# main.net
KiCad netlist of a schematic drawn in EAGLE
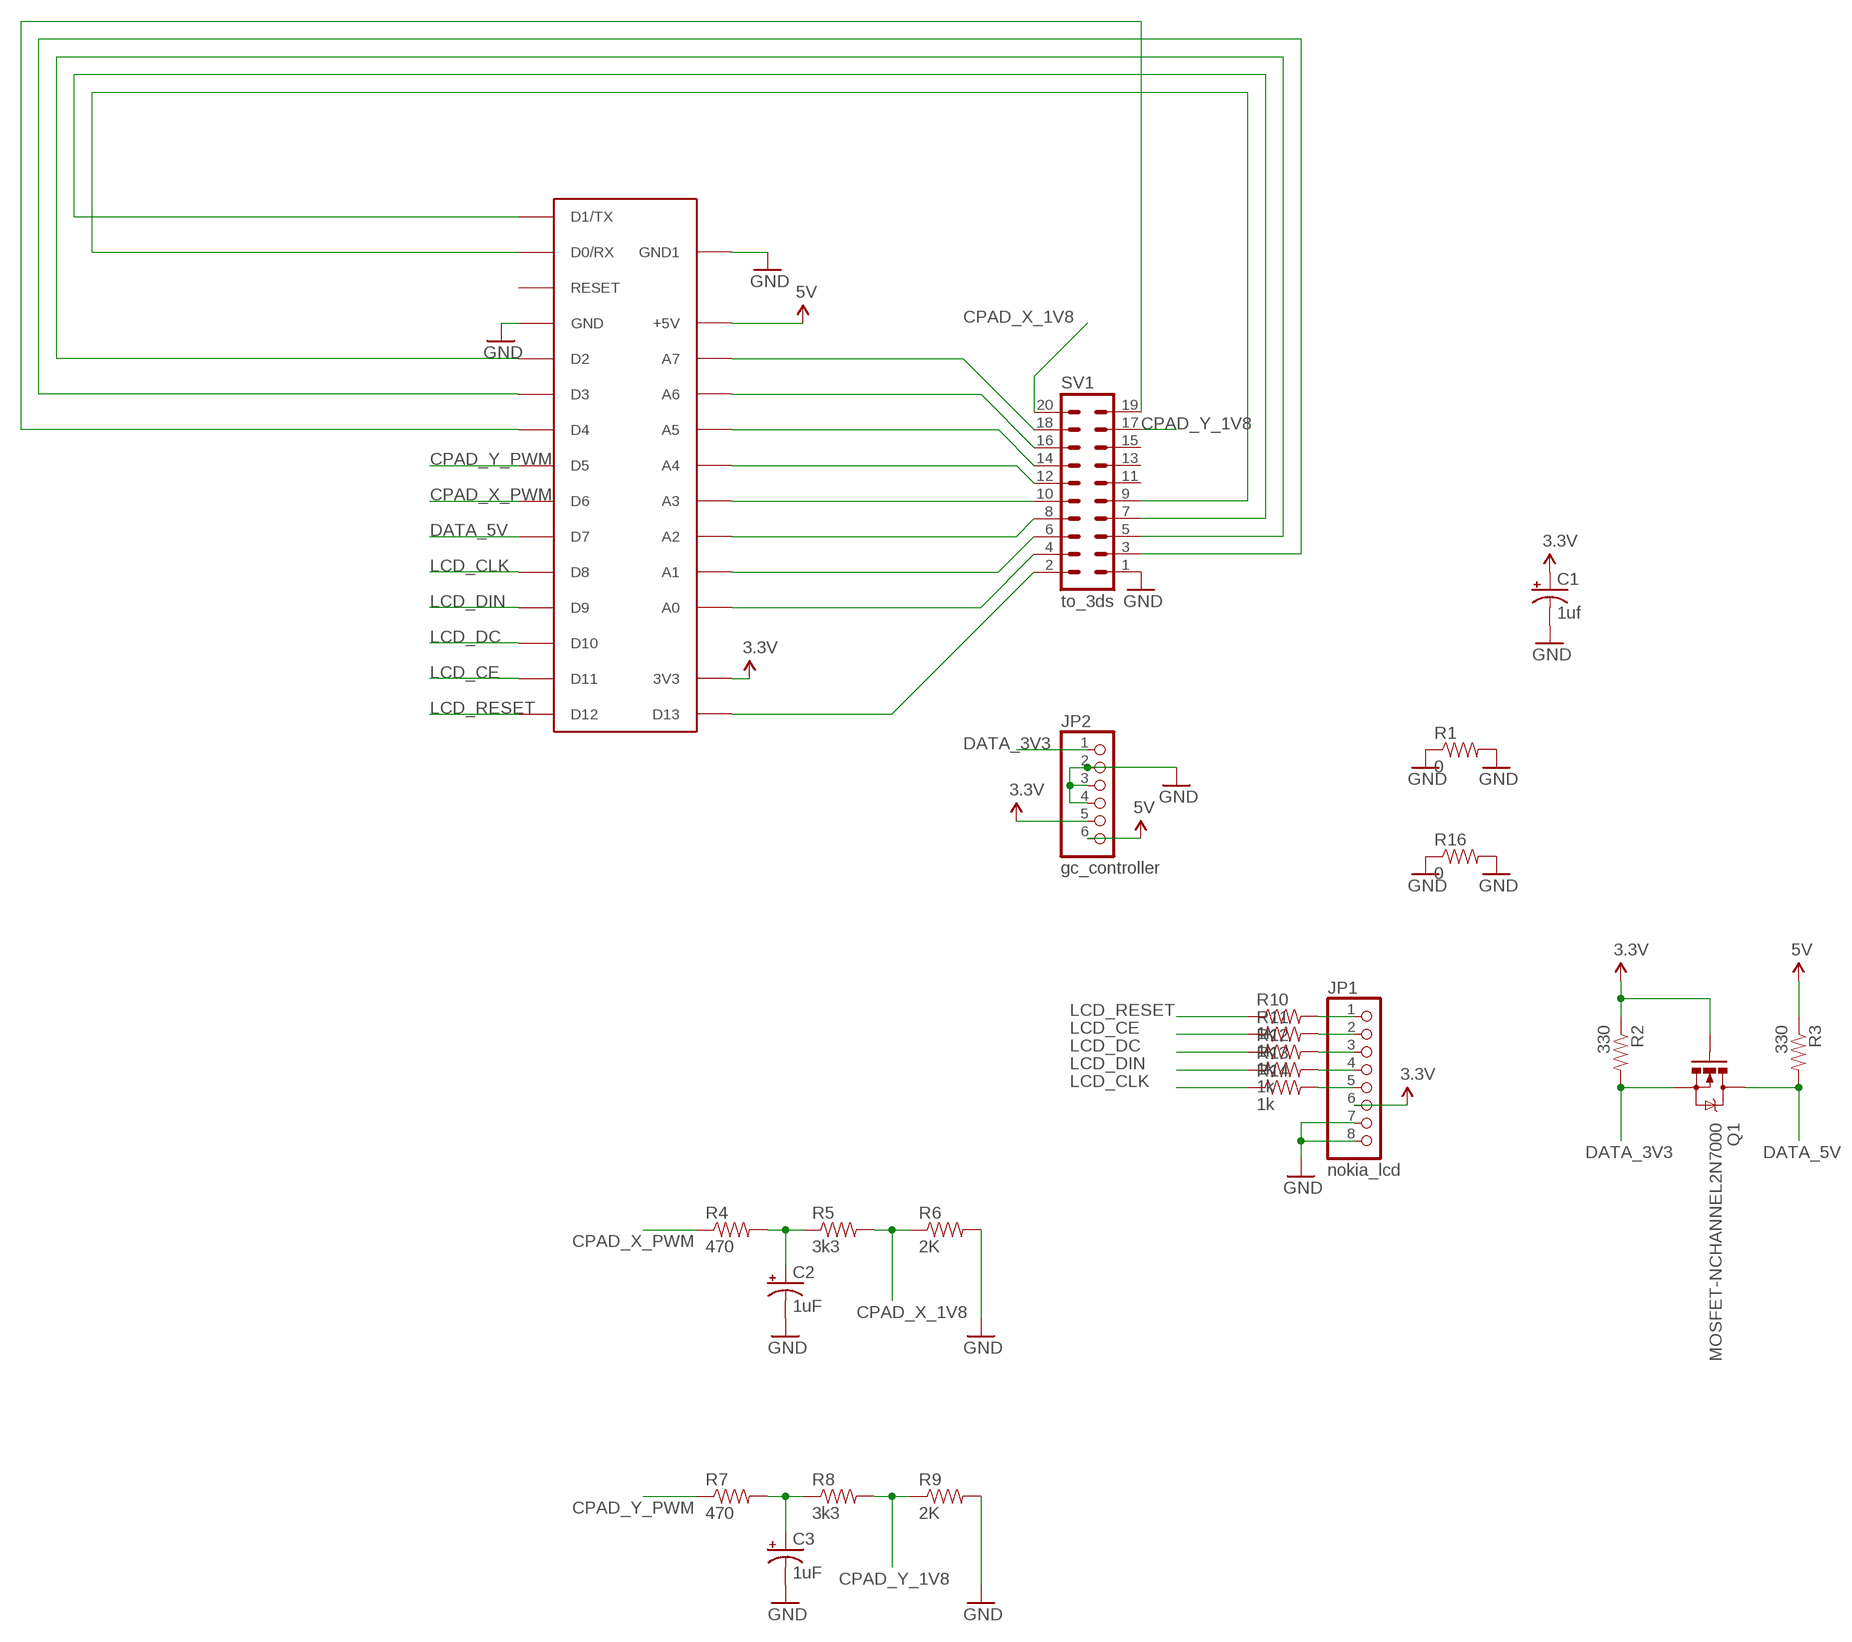
[diagram p0: schematic, sheet 1]

(export (version "E")
  (design (tool "Eeschema 10.0.6"))
  (components
    (comp (ref "C1")
      (value "1uf")
      (footprint "eagle-import:CPOL-RADIAL-10UF-25V")
      (libsource (lib "eagle-import") (part "CAP_POLPTH2"))
    )
    (comp (ref "C2")
      (value "1uF")
      (footprint "eagle-import:CPOL-RADIAL-10UF-25V")
      (libsource (lib "eagle-import") (part "CAP_POLPTH2"))
    )
    (comp (ref "C3")
      (value "1uF")
      (footprint "eagle-import:CPOL-RADIAL-10UF-25V")
      (libsource (lib "eagle-import") (part "CAP_POLPTH2"))
    )
    (comp (ref "JP1")
      (value "nokia_lcd")
      (footprint "eagle-import:1X08-CLEANBIG")
      (libsource (lib "eagle-import") (part "PINHD-1X8CLEANBIG"))
    )
    (comp (ref "JP2")
      (value "gc_controller")
      (footprint "eagle-import:1X06")
      (libsource (lib "eagle-import") (part "PINHD-1X6"))
    )
    (comp (ref "Q1")
      (value "MOSFET-NCHANNEL2N7000")
      (footprint "eagle-import:TO-92")
      (libsource (lib "eagle-import") (part "MOSFET-NCHANNEL2N7000"))
    )
    (comp (ref "R1")
      (value "0")
      (footprint "eagle-import:AXIAL-0.4")
      (libsource (lib "eagle-import") (part "RESISTORPTH-1/4W"))
    )
    (comp (ref "R2")
      (value "330")
      (footprint "eagle-import:AXIAL-0.4")
      (libsource (lib "eagle-import") (part "RESISTORPTH-1/4W"))
    )
    (comp (ref "R3")
      (value "330")
      (footprint "eagle-import:AXIAL-0.4")
      (libsource (lib "eagle-import") (part "RESISTORPTH-1/4W"))
    )
    (comp (ref "R4")
      (value "470")
      (footprint "eagle-import:AXIAL-0.4")
      (libsource (lib "eagle-import") (part "RESISTORPTH-1/4W"))
    )
    (comp (ref "R5")
      (value "3k3")
      (footprint "eagle-import:AXIAL-0.4")
      (libsource (lib "eagle-import") (part "RESISTORPTH-1/4W"))
    )
    (comp (ref "R6")
      (value "2K")
      (footprint "eagle-import:AXIAL-0.4")
      (libsource (lib "eagle-import") (part "RESISTORPTH-1/4W"))
    )
    (comp (ref "R7")
      (value "470")
      (footprint "eagle-import:AXIAL-0.4")
      (libsource (lib "eagle-import") (part "RESISTORPTH-1/4W"))
    )
    (comp (ref "R8")
      (value "3k3")
      (footprint "eagle-import:AXIAL-0.4")
      (libsource (lib "eagle-import") (part "RESISTORPTH-1/4W"))
    )
    (comp (ref "R9")
      (value "2K")
      (footprint "eagle-import:AXIAL-0.4")
      (libsource (lib "eagle-import") (part "RESISTORPTH-1/4W"))
    )
    (comp (ref "R10")
      (value "1k")
      (footprint "eagle-import:AXIAL-0.4")
      (libsource (lib "eagle-import") (part "RESISTORPTH-1/4W"))
    )
    (comp (ref "R11")
      (value "1k")
      (footprint "eagle-import:AXIAL-0.4")
      (libsource (lib "eagle-import") (part "RESISTORPTH-1/4W"))
    )
    (comp (ref "R12")
      (value "1k")
      (footprint "eagle-import:AXIAL-0.4")
      (libsource (lib "eagle-import") (part "RESISTORPTH-1/4W"))
    )
    (comp (ref "R13")
      (value "1k")
      (footprint "eagle-import:AXIAL-0.4")
      (libsource (lib "eagle-import") (part "RESISTORPTH-1/4W"))
    )
    (comp (ref "R14")
      (value "1k")
      (footprint "eagle-import:AXIAL-0.4")
      (libsource (lib "eagle-import") (part "RESISTORPTH-1/4W"))
    )
    (comp (ref "R16")
      (value "0")
      (footprint "eagle-import:AXIAL-0.4")
      (libsource (lib "eagle-import") (part "RESISTORPTH-1/4W"))
    )
    (comp (ref "SV1")
      (value "to_3ds")
      (footprint "eagle-import:MA10-2")
      (libsource (lib "eagle-import") (part "MA10-2"))
    )
    (comp (ref "U$1")
      (value "ARDUINONANO")
      (footprint "eagle-import:PDIP-32")
      (libsource (lib "eagle-import") (part "ARDUINONANO"))
    )
  )
  (nets
    (net (code "1") (name "/CPAD_X_1V8") (class "Default")
      (node (ref "R5") (pin "P$2") (pinfunction "2_P$2") (pintype "passive"))
      (node (ref "R6") (pin "P$1") (pinfunction "1_P$1") (pintype "passive"))
      (node (ref "SV1") (pin "20") (pinfunction "20_20") (pintype "passive"))
    )
    (net (code "2") (name "/CPAD_X_PWM") (class "Default")
      (node (ref "R4") (pin "P$1") (pinfunction "1_P$1") (pintype "passive"))
      (node (ref "U$1") (pin "D6") (pinfunction "D6_D6") (pintype "bidirectional"))
    )
    (net (code "3") (name "/CPAD_Y_1V8") (class "Default")
      (node (ref "R8") (pin "P$2") (pinfunction "2_P$2") (pintype "passive"))
      (node (ref "R9") (pin "P$1") (pinfunction "1_P$1") (pintype "passive"))
      (node (ref "SV1") (pin "17") (pinfunction "17_17") (pintype "passive"))
    )
    (net (code "4") (name "/CPAD_Y_PWM") (class "Default")
      (node (ref "R7") (pin "P$1") (pinfunction "1_P$1") (pintype "passive"))
      (node (ref "U$1") (pin "D5") (pinfunction "D5_D5") (pintype "bidirectional"))
    )
    (net (code "5") (name "/DATA_3V3") (class "Default")
      (node (ref "JP2") (pin "1") (pinfunction "1_1") (pintype "passive"))
      (node (ref "Q1") (pin "1") (pinfunction "S_1") (pintype "passive"))
      (node (ref "R2") (pin "P$2") (pinfunction "2_P$2") (pintype "passive"))
    )
    (net (code "6") (name "/DATA_5V") (class "Default")
      (node (ref "Q1") (pin "3") (pinfunction "D_3") (pintype "passive"))
      (node (ref "R3") (pin "P$2") (pinfunction "2_P$2") (pintype "passive"))
      (node (ref "U$1") (pin "D7") (pinfunction "D7_D7") (pintype "bidirectional"))
    )
    (net (code "7") (name "/LCD_CE") (class "Default")
      (node (ref "R11") (pin "P$1") (pinfunction "1_P$1") (pintype "passive"))
      (node (ref "U$1") (pin "D11") (pinfunction "D11_D11") (pintype "bidirectional"))
    )
    (net (code "8") (name "/LCD_CLK") (class "Default")
      (node (ref "R14") (pin "P$1") (pinfunction "1_P$1") (pintype "passive"))
      (node (ref "U$1") (pin "D8") (pinfunction "D8_D8") (pintype "bidirectional"))
    )
    (net (code "9") (name "/LCD_DC") (class "Default")
      (node (ref "R12") (pin "P$1") (pinfunction "1_P$1") (pintype "passive"))
      (node (ref "U$1") (pin "D10") (pinfunction "D10_D10") (pintype "bidirectional"))
    )
    (net (code "10") (name "/LCD_DIN") (class "Default")
      (node (ref "R13") (pin "P$1") (pinfunction "1_P$1") (pintype "passive"))
      (node (ref "U$1") (pin "D9") (pinfunction "D9_D9") (pintype "bidirectional"))
    )
    (net (code "11") (name "/LCD_RESET") (class "Default")
      (node (ref "R10") (pin "P$1") (pinfunction "1_P$1") (pintype "passive"))
      (node (ref "U$1") (pin "D12") (pinfunction "D12_D12") (pintype "bidirectional"))
    )
    (net (code "12") (name "3.3V") (class "Default")
      (node (ref "C1") (pin "1") (pinfunction "+_1") (pintype "passive"))
      (node (ref "JP1") (pin "6") (pinfunction "6_6") (pintype "passive"))
      (node (ref "JP2") (pin "5") (pinfunction "5_5") (pintype "passive"))
      (node (ref "Q1") (pin "2") (pinfunction "G_2") (pintype "passive"))
      (node (ref "R2") (pin "P$1") (pinfunction "1_P$1") (pintype "passive"))
      (node (ref "U$1") (pin "3V3") (pinfunction "3V3_3V3") (pintype "bidirectional"))
    )
    (net (code "13") (name "5V") (class "Default")
      (node (ref "JP2") (pin "6") (pinfunction "6_6") (pintype "passive"))
      (node (ref "R3") (pin "P$1") (pinfunction "1_P$1") (pintype "passive"))
      (node (ref "U$1") (pin "+5V") (pinfunction "+5V_+5V") (pintype "bidirectional"))
    )
    (net (code "14") (name "GND") (class "Default")
      (node (ref "C1") (pin "2") (pinfunction "-_2") (pintype "passive"))
      (node (ref "C2") (pin "2") (pinfunction "-_2") (pintype "passive"))
      (node (ref "C3") (pin "2") (pinfunction "-_2") (pintype "passive"))
      (node (ref "JP1") (pin "7") (pinfunction "7_7") (pintype "passive"))
      (node (ref "JP1") (pin "8") (pinfunction "8_8") (pintype "passive"))
      (node (ref "JP2") (pin "2") (pinfunction "2_2") (pintype "passive"))
      (node (ref "JP2") (pin "3") (pinfunction "3_3") (pintype "passive"))
      (node (ref "JP2") (pin "4") (pinfunction "4_4") (pintype "passive"))
      (node (ref "R1") (pin "P$1") (pinfunction "1_P$1") (pintype "passive"))
      (node (ref "R1") (pin "P$2") (pinfunction "2_P$2") (pintype "passive"))
      (node (ref "R16") (pin "P$1") (pinfunction "1_P$1") (pintype "passive"))
      (node (ref "R16") (pin "P$2") (pinfunction "2_P$2") (pintype "passive"))
      (node (ref "R6") (pin "P$2") (pinfunction "2_P$2") (pintype "passive"))
      (node (ref "R9") (pin "P$2") (pinfunction "2_P$2") (pintype "passive"))
      (node (ref "SV1") (pin "1") (pinfunction "1_1") (pintype "passive"))
      (node (ref "U$1") (pin "GND") (pinfunction "GND_GND") (pintype "bidirectional"))
      (node (ref "U$1") (pin "GND1") (pinfunction "GND1_GND1") (pintype "bidirectional"))
    )
    (net (code "15") (name "Net-(C2-+)") (class "Default")
      (node (ref "C2") (pin "1") (pinfunction "+_1") (pintype "passive"))
      (node (ref "R4") (pin "P$2") (pinfunction "2_P$2") (pintype "passive"))
      (node (ref "R5") (pin "P$1") (pinfunction "1_P$1") (pintype "passive"))
    )
    (net (code "16") (name "Net-(C3-+)") (class "Default")
      (node (ref "C3") (pin "1") (pinfunction "+_1") (pintype "passive"))
      (node (ref "R7") (pin "P$2") (pinfunction "2_P$2") (pintype "passive"))
      (node (ref "R8") (pin "P$1") (pinfunction "1_P$1") (pintype "passive"))
    )
    (net (code "17") (name "Net-(R10-2)") (class "Default")
      (node (ref "JP1") (pin "1") (pinfunction "1_1") (pintype "passive"))
      (node (ref "R10") (pin "P$2") (pinfunction "2_P$2") (pintype "passive"))
    )
    (net (code "18") (name "Net-(R11-2)") (class "Default")
      (node (ref "JP1") (pin "2") (pinfunction "2_2") (pintype "passive"))
      (node (ref "R11") (pin "P$2") (pinfunction "2_P$2") (pintype "passive"))
    )
    (net (code "19") (name "Net-(R12-2)") (class "Default")
      (node (ref "JP1") (pin "3") (pinfunction "3_3") (pintype "passive"))
      (node (ref "R12") (pin "P$2") (pinfunction "2_P$2") (pintype "passive"))
    )
    (net (code "20") (name "Net-(R13-2)") (class "Default")
      (node (ref "JP1") (pin "4") (pinfunction "4_4") (pintype "passive"))
      (node (ref "R13") (pin "P$2") (pinfunction "2_P$2") (pintype "passive"))
    )
    (net (code "21") (name "Net-(R14-2)") (class "Default")
      (node (ref "JP1") (pin "5") (pinfunction "5_5") (pintype "passive"))
      (node (ref "R14") (pin "P$2") (pinfunction "2_P$2") (pintype "passive"))
    )
    (net (code "22") (name "Net-(SV1-Pad2)") (class "Default")
      (node (ref "SV1") (pin "2") (pinfunction "2_2") (pintype "passive"))
      (node (ref "U$1") (pin "D13") (pinfunction "D13_D13") (pintype "bidirectional"))
    )
    (net (code "23") (name "Net-(SV1-Pad3)") (class "Default")
      (node (ref "SV1") (pin "3") (pinfunction "3_3") (pintype "passive"))
      (node (ref "U$1") (pin "D3") (pinfunction "D3_D3") (pintype "bidirectional"))
    )
    (net (code "24") (name "Net-(SV1-Pad4)") (class "Default")
      (node (ref "SV1") (pin "4") (pinfunction "4_4") (pintype "passive"))
      (node (ref "U$1") (pin "A0") (pinfunction "A0_A0") (pintype "bidirectional"))
    )
    (net (code "25") (name "Net-(SV1-Pad5)") (class "Default")
      (node (ref "SV1") (pin "5") (pinfunction "5_5") (pintype "passive"))
      (node (ref "U$1") (pin "D2") (pinfunction "D2_D2") (pintype "bidirectional"))
    )
    (net (code "26") (name "Net-(SV1-Pad6)") (class "Default")
      (node (ref "SV1") (pin "6") (pinfunction "6_6") (pintype "passive"))
      (node (ref "U$1") (pin "A1") (pinfunction "A1_A1") (pintype "bidirectional"))
    )
    (net (code "27") (name "Net-(SV1-Pad7)") (class "Default")
      (node (ref "SV1") (pin "7") (pinfunction "7_7") (pintype "passive"))
      (node (ref "U$1") (pin "D1/TX") (pinfunction "D1/TX_D1/TX") (pintype "bidirectional"))
    )
    (net (code "28") (name "Net-(SV1-Pad8)") (class "Default")
      (node (ref "SV1") (pin "8") (pinfunction "8_8") (pintype "passive"))
      (node (ref "U$1") (pin "A2") (pinfunction "A2_A2") (pintype "bidirectional"))
    )
    (net (code "29") (name "Net-(SV1-Pad9)") (class "Default")
      (node (ref "SV1") (pin "9") (pinfunction "9_9") (pintype "passive"))
      (node (ref "U$1") (pin "D0/RX") (pinfunction "D0/RX_D0/RX") (pintype "bidirectional"))
    )
    (net (code "30") (name "Net-(SV1-Pad10)") (class "Default")
      (node (ref "SV1") (pin "10") (pinfunction "10_10") (pintype "passive"))
      (node (ref "U$1") (pin "A3") (pinfunction "A3_A3") (pintype "bidirectional"))
    )
    (net (code "31") (name "Net-(SV1-Pad12)") (class "Default")
      (node (ref "SV1") (pin "12") (pinfunction "12_12") (pintype "passive"))
      (node (ref "U$1") (pin "A4") (pinfunction "A4_A4") (pintype "bidirectional"))
    )
    (net (code "32") (name "Net-(SV1-Pad14)") (class "Default")
      (node (ref "SV1") (pin "14") (pinfunction "14_14") (pintype "passive"))
      (node (ref "U$1") (pin "A5") (pinfunction "A5_A5") (pintype "bidirectional"))
    )
    (net (code "33") (name "Net-(SV1-Pad16)") (class "Default")
      (node (ref "SV1") (pin "16") (pinfunction "16_16") (pintype "passive"))
      (node (ref "U$1") (pin "A6") (pinfunction "A6_A6") (pintype "bidirectional"))
    )
    (net (code "34") (name "Net-(SV1-Pad18)") (class "Default")
      (node (ref "SV1") (pin "18") (pinfunction "18_18") (pintype "passive"))
      (node (ref "U$1") (pin "A7") (pinfunction "A7_A7") (pintype "bidirectional"))
    )
    (net (code "35") (name "Net-(SV1-Pad19)") (class "Default")
      (node (ref "SV1") (pin "19") (pinfunction "19_19") (pintype "passive"))
      (node (ref "U$1") (pin "D4") (pinfunction "D4_D4") (pintype "bidirectional"))
    )
    (net (code "36") (name "unconnected-(SV1-Pad11)") (class "Default")
      (node (ref "SV1") (pin "11") (pinfunction "11_11") (pintype "passive"))
    )
    (net (code "37") (name "unconnected-(SV1-Pad13)") (class "Default")
      (node (ref "SV1") (pin "13") (pinfunction "13_13") (pintype "passive"))
    )
    (net (code "38") (name "unconnected-(SV1-Pad15)") (class "Default")
      (node (ref "SV1") (pin "15") (pinfunction "15_15") (pintype "passive"))
    )
    (net (code "39") (name "unconnected-(U$1-PadRESET)") (class "Default")
      (node (ref "U$1") (pin "RESET") (pinfunction "RESET_RESET") (pintype "bidirectional"))
    )
  )
)
